# 4port.net
KiCad netlist of a schematic drawn in EAGLE
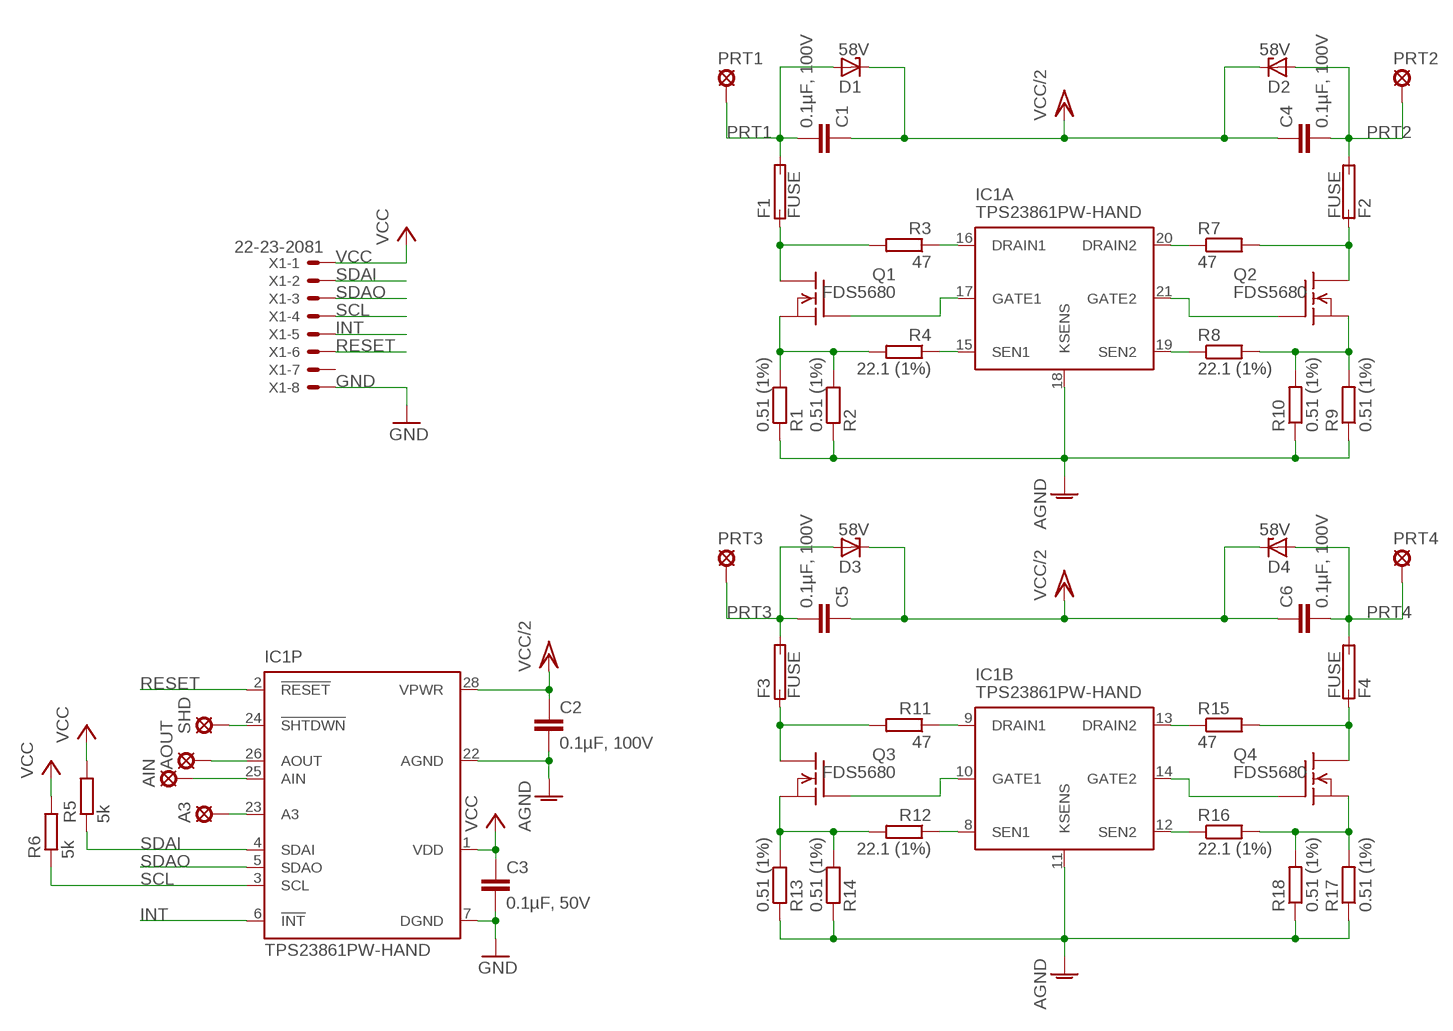
[diagram p0: schematic, sheet 1]
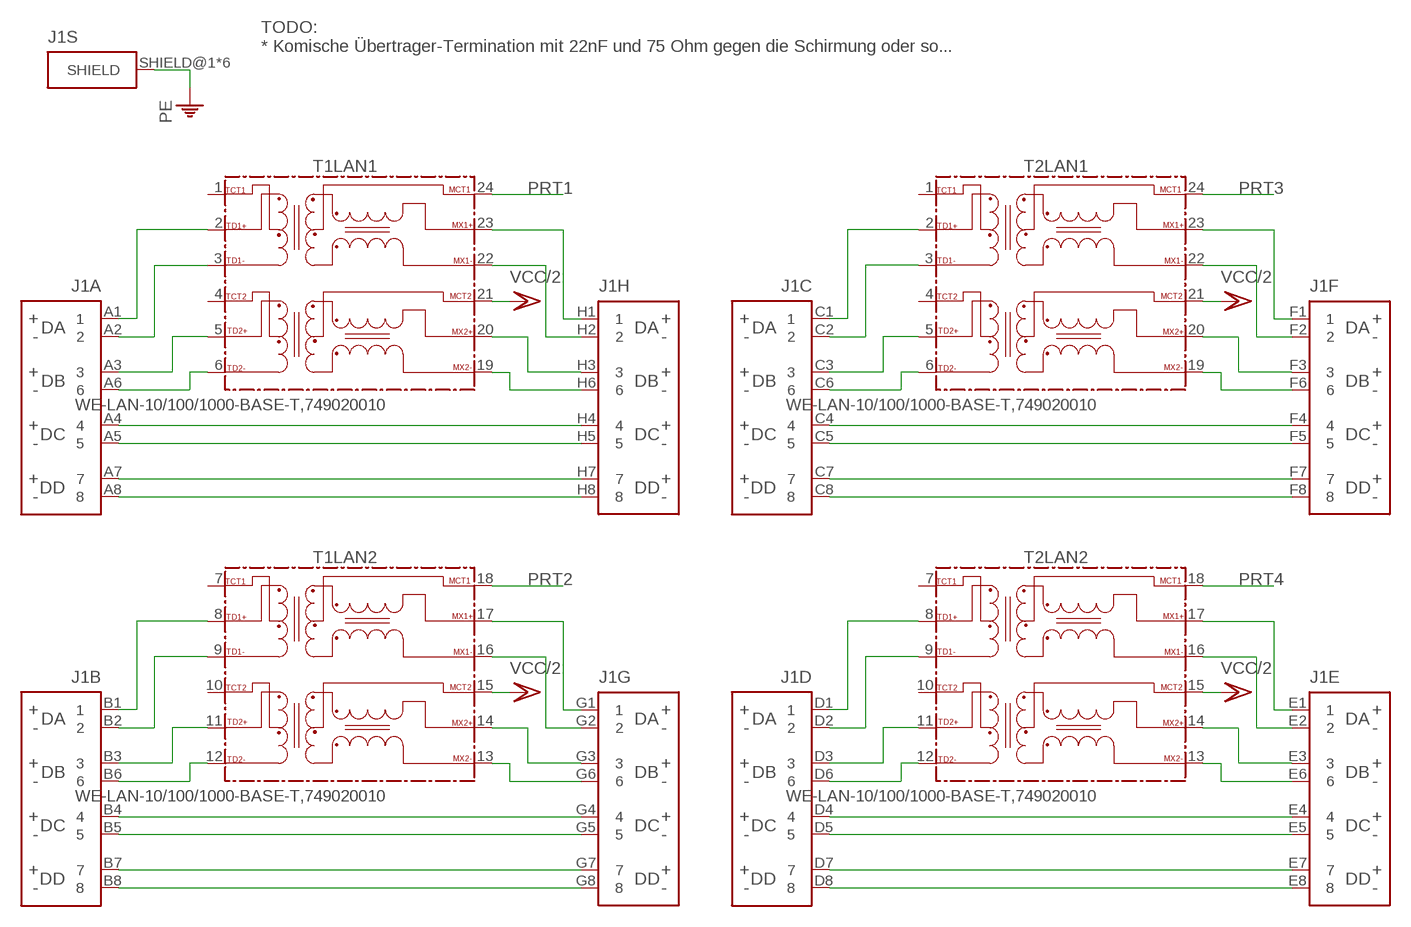
[diagram p1: schematic, sheet 2]
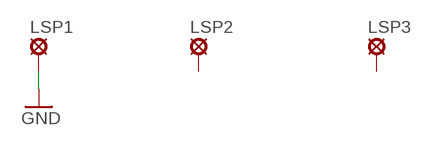
[diagram p2: schematic, sheet 3]

(export (version "E")
  (design (tool "Eeschema 10.0.6"))
  (components
    (comp (ref "J1")
      (value "615064243321")
      (footprint "eagle-import:615064243321")
      (libsource (lib "eagle-import") (part "615064243321"))
    )
    (comp (ref "T1")
      (value "WE-LAN-10/100/1000-BASE-T,749020010")
      (footprint "eagle-import:749020010")
      (fields
        (field (name "MANUFACTURER") "Würth Elektronik eiSos GmbH")
        (field (name "CREATED-BY") "Christin Zierenner")
      )
      (libsource (lib "eagle-import") (part "WE-LAN-10/100/1000-BASE-T,749020010"))
    )
    (comp (ref "T2")
      (value "WE-LAN-10/100/1000-BASE-T,749020010")
      (footprint "eagle-import:749020010")
      (fields
        (field (name "MANUFACTURER") "Würth Elektronik eiSos GmbH")
        (field (name "CREATED-BY") "Christin Zierenner")
      )
      (libsource (lib "eagle-import") (part "WE-LAN-10/100/1000-BASE-T,749020010"))
    )
    (comp (ref "A3")
      (value "SE14")
      (footprint "eagle-import:SE14")
      (libsource (lib "eagle-import") (part "SE14"))
    )
    (comp (ref "AIN")
      (value "SE14")
      (footprint "eagle-import:SE14")
      (libsource (lib "eagle-import") (part "SE14"))
    )
    (comp (ref "AOUT")
      (value "SE14")
      (footprint "eagle-import:SE14")
      (libsource (lib "eagle-import") (part "SE14"))
    )
    (comp (ref "C1")
      (value "0.1µF, 100V")
      (footprint "eagle-import:C0805K")
      (libsource (lib "eagle-import") (part "C-EUC0805K"))
    )
    (comp (ref "C2")
      (value "0.1µF, 100V")
      (footprint "eagle-import:C0805K")
      (libsource (lib "eagle-import") (part "C-EUC0805K"))
    )
    (comp (ref "C3")
      (value "0.1µF, 50V")
      (footprint "eagle-import:C0805K")
      (libsource (lib "eagle-import") (part "C-EUC0805K"))
    )
    (comp (ref "C4")
      (value "0.1µF, 100V")
      (footprint "eagle-import:C0805K")
      (libsource (lib "eagle-import") (part "C-EUC0805K"))
    )
    (comp (ref "C5")
      (value "0.1µF, 100V")
      (footprint "eagle-import:C0805K")
      (libsource (lib "eagle-import") (part "C-EUC0805K"))
    )
    (comp (ref "C6")
      (value "0.1µF, 100V")
      (footprint "eagle-import:C0805K")
      (libsource (lib "eagle-import") (part "C-EUC0805K"))
    )
    (comp (ref "D1")
      (value "58V")
      (footprint "eagle-import:SMB")
      (libsource (lib "eagle-import") (part "ZENER-DIODESMB"))
    )
    (comp (ref "D2")
      (value "58V")
      (footprint "eagle-import:SMB")
      (libsource (lib "eagle-import") (part "ZENER-DIODESMB"))
    )
    (comp (ref "D3")
      (value "58V")
      (footprint "eagle-import:SMB")
      (libsource (lib "eagle-import") (part "ZENER-DIODESMB"))
    )
    (comp (ref "D4")
      (value "58V")
      (footprint "eagle-import:SMB")
      (libsource (lib "eagle-import") (part "ZENER-DIODESMB"))
    )
    (comp (ref "F1")
      (value "FUSE")
      (footprint "eagle-import:R1206W")
      (libsource (lib "eagle-import") (part "FUSE"))
    )
    (comp (ref "F2")
      (value "FUSE")
      (footprint "eagle-import:R1206W")
      (libsource (lib "eagle-import") (part "FUSE"))
    )
    (comp (ref "F3")
      (value "FUSE")
      (footprint "eagle-import:R1206W")
      (libsource (lib "eagle-import") (part "FUSE"))
    )
    (comp (ref "F4")
      (value "FUSE")
      (footprint "eagle-import:R1206W")
      (libsource (lib "eagle-import") (part "FUSE"))
    )
    (comp (ref "IC1")
      (value "TPS23861PW-HAND")
      (footprint "eagle-import:PW_R-PDSO-G28_HAND")
      (libsource (lib "eagle-import") (part "TPS23861PW-HAND"))
    )
    (comp (ref "PRT1")
      (value "SE14")
      (footprint "eagle-import:SE14")
      (libsource (lib "eagle-import") (part "SE14"))
    )
    (comp (ref "PRT2")
      (value "SE14")
      (footprint "eagle-import:SE14")
      (libsource (lib "eagle-import") (part "SE14"))
    )
    (comp (ref "PRT3")
      (value "SE14")
      (footprint "eagle-import:SE14")
      (libsource (lib "eagle-import") (part "SE14"))
    )
    (comp (ref "PRT4")
      (value "SE14")
      (footprint "eagle-import:SE14")
      (libsource (lib "eagle-import") (part "SE14"))
    )
    (comp (ref "Q1")
      (value "FDS5680")
      (footprint "eagle-import:SO-8")
      (libsource (lib "eagle-import") (part "FDS5680"))
    )
    (comp (ref "Q2")
      (value "FDS5680")
      (footprint "eagle-import:SO-8")
      (libsource (lib "eagle-import") (part "FDS5680"))
    )
    (comp (ref "Q3")
      (value "FDS5680")
      (footprint "eagle-import:SO-8")
      (libsource (lib "eagle-import") (part "FDS5680"))
    )
    (comp (ref "Q4")
      (value "FDS5680")
      (footprint "eagle-import:SO-8")
      (libsource (lib "eagle-import") (part "FDS5680"))
    )
    (comp (ref "R1")
      (value "0.51 (1%)")
      (footprint "eagle-import:R0603")
      (libsource (lib "eagle-import") (part "R-EU_R0603"))
    )
    (comp (ref "R2")
      (value "0.51 (1%)")
      (footprint "eagle-import:R0603")
      (libsource (lib "eagle-import") (part "R-EU_R0603"))
    )
    (comp (ref "R3")
      (value "47")
      (footprint "eagle-import:R0603")
      (libsource (lib "eagle-import") (part "R-EU_R0603"))
    )
    (comp (ref "R4")
      (value "22.1 (1%)")
      (footprint "eagle-import:R0603")
      (libsource (lib "eagle-import") (part "R-EU_R0603"))
    )
    (comp (ref "R5")
      (value "5k")
      (footprint "eagle-import:R0805W")
      (libsource (lib "eagle-import") (part "R-EU_R0805W"))
    )
    (comp (ref "R6")
      (value "5k")
      (footprint "eagle-import:R0805W")
      (libsource (lib "eagle-import") (part "R-EU_R0805W"))
    )
    (comp (ref "R7")
      (value "47")
      (footprint "eagle-import:R0603")
      (libsource (lib "eagle-import") (part "R-EU_R0603"))
    )
    (comp (ref "R8")
      (value "22.1 (1%)")
      (footprint "eagle-import:R0603")
      (libsource (lib "eagle-import") (part "R-EU_R0603"))
    )
    (comp (ref "R9")
      (value "0.51 (1%)")
      (footprint "eagle-import:R0603")
      (libsource (lib "eagle-import") (part "R-EU_R0603"))
    )
    (comp (ref "R10")
      (value "0.51 (1%)")
      (footprint "eagle-import:R0603")
      (libsource (lib "eagle-import") (part "R-EU_R0603"))
    )
    (comp (ref "R11")
      (value "47")
      (footprint "eagle-import:R0603")
      (libsource (lib "eagle-import") (part "R-EU_R0603"))
    )
    (comp (ref "R12")
      (value "22.1 (1%)")
      (footprint "eagle-import:R0603")
      (libsource (lib "eagle-import") (part "R-EU_R0603"))
    )
    (comp (ref "R13")
      (value "0.51 (1%)")
      (footprint "eagle-import:R0603")
      (libsource (lib "eagle-import") (part "R-EU_R0603"))
    )
    (comp (ref "R14")
      (value "0.51 (1%)")
      (footprint "eagle-import:R0603")
      (libsource (lib "eagle-import") (part "R-EU_R0603"))
    )
    (comp (ref "R15")
      (value "47")
      (footprint "eagle-import:R0603")
      (libsource (lib "eagle-import") (part "R-EU_R0603"))
    )
    (comp (ref "R16")
      (value "22.1 (1%)")
      (footprint "eagle-import:R0603")
      (libsource (lib "eagle-import") (part "R-EU_R0603"))
    )
    (comp (ref "R17")
      (value "0.51 (1%)")
      (footprint "eagle-import:R0603")
      (libsource (lib "eagle-import") (part "R-EU_R0603"))
    )
    (comp (ref "R18")
      (value "0.51 (1%)")
      (footprint "eagle-import:R0603")
      (libsource (lib "eagle-import") (part "R-EU_R0603"))
    )
    (comp (ref "SHD")
      (value "SE14")
      (footprint "eagle-import:SE14")
      (libsource (lib "eagle-import") (part "SE14"))
    )
    (comp (ref "X1")
      (value "22-23-2081")
      (footprint "eagle-import:22-23-2081")
      (fields (field (name "MF") "MOLEX"))
      (libsource (lib "eagle-import") (part "22-23-2081"))
    )
    (comp (ref "LSP1")
      (value "SE14")
      (footprint "eagle-import:SE14")
      (libsource (lib "eagle-import") (part "SE14"))
    )
    (comp (ref "LSP2")
      (value "SE14")
      (footprint "eagle-import:SE14")
      (libsource (lib "eagle-import") (part "SE14"))
    )
    (comp (ref "LSP3")
      (value "SE14")
      (footprint "eagle-import:SE14")
      (libsource (lib "eagle-import") (part "SE14"))
    )
  )
  (nets
    (net (code "1") (name "AGND") (class "Default")
      (node (ref "C2") (pin "2") (pinfunction "2_2") (pintype "passive"))
      (node (ref "IC1") (pin "11") (pinfunction "KSENS_11") (pintype "input"))
      (node (ref "IC1") (pin "18") (pinfunction "KSENS_18") (pintype "input"))
      (node (ref "IC1") (pin "22") (pinfunction "AGND_22") (pintype "power_in"))
      (node (ref "R1") (pin "1") (pinfunction "1_1") (pintype "passive"))
      (node (ref "R10") (pin "1") (pinfunction "1_1") (pintype "passive"))
      (node (ref "R13") (pin "1") (pinfunction "1_1") (pintype "passive"))
      (node (ref "R14") (pin "1") (pinfunction "1_1") (pintype "passive"))
      (node (ref "R17") (pin "1") (pinfunction "1_1") (pintype "passive"))
      (node (ref "R18") (pin "1") (pinfunction "1_1") (pintype "passive"))
      (node (ref "R2") (pin "1") (pinfunction "1_1") (pintype "passive"))
      (node (ref "R9") (pin "1") (pinfunction "1_1") (pintype "passive"))
    )
    (net (code "2") (name "GND") (class "Default")
      (node (ref "C3") (pin "2") (pinfunction "2_2") (pintype "passive"))
      (node (ref "IC1") (pin "7") (pinfunction "DGND_7") (pintype "power_in"))
      (node (ref "LSP1") (pin "MP") (pinfunction "MP_MP") (pintype "passive"))
      (node (ref "X1") (pin "8") (pinfunction "S_8") (pintype "passive"))
    )
    (net (code "3") (name "INT") (class "Default")
      (node (ref "IC1") (pin "6") (pinfunction "~{INT}_6") (pintype "output"))
      (node (ref "X1") (pin "5") (pinfunction "S_5") (pintype "passive"))
    )
    (net (code "4") (name "Net-(F1-1A)") (class "Default")
      (node (ref "F1") (pin "1") (pinfunction "1A_1") (pintype "passive"))
      (node (ref "Q1") (pin "5") (pinfunction "D_5") (pintype "passive"))
      (node (ref "Q1") (pin "6") (pinfunction "D_6") (pintype "passive"))
      (node (ref "Q1") (pin "7") (pinfunction "D_7") (pintype "passive"))
      (node (ref "Q1") (pin "8") (pinfunction "D_8") (pintype "passive"))
      (node (ref "R3") (pin "2") (pinfunction "2_2") (pintype "passive"))
    )
    (net (code "5") (name "Net-(F2-1A)") (class "Default")
      (node (ref "F2") (pin "1") (pinfunction "1A_1") (pintype "passive"))
      (node (ref "Q2") (pin "5") (pinfunction "D_5") (pintype "passive"))
      (node (ref "Q2") (pin "6") (pinfunction "D_6") (pintype "passive"))
      (node (ref "Q2") (pin "7") (pinfunction "D_7") (pintype "passive"))
      (node (ref "Q2") (pin "8") (pinfunction "D_8") (pintype "passive"))
      (node (ref "R7") (pin "2") (pinfunction "2_2") (pintype "passive"))
    )
    (net (code "6") (name "Net-(F3-1A)") (class "Default")
      (node (ref "F3") (pin "1") (pinfunction "1A_1") (pintype "passive"))
      (node (ref "Q3") (pin "5") (pinfunction "D_5") (pintype "passive"))
      (node (ref "Q3") (pin "6") (pinfunction "D_6") (pintype "passive"))
      (node (ref "Q3") (pin "7") (pinfunction "D_7") (pintype "passive"))
      (node (ref "Q3") (pin "8") (pinfunction "D_8") (pintype "passive"))
      (node (ref "R11") (pin "2") (pinfunction "2_2") (pintype "passive"))
    )
    (net (code "7") (name "Net-(F4-1A)") (class "Default")
      (node (ref "F4") (pin "1") (pinfunction "1A_1") (pintype "passive"))
      (node (ref "Q4") (pin "5") (pinfunction "D_5") (pintype "passive"))
      (node (ref "Q4") (pin "6") (pinfunction "D_6") (pintype "passive"))
      (node (ref "Q4") (pin "7") (pinfunction "D_7") (pintype "passive"))
      (node (ref "Q4") (pin "8") (pinfunction "D_8") (pintype "passive"))
      (node (ref "R15") (pin "2") (pinfunction "2_2") (pintype "passive"))
    )
    (net (code "8") (name "Net-(IC1A-DRAIN1)") (class "Default")
      (node (ref "IC1") (pin "16") (pinfunction "DRAIN1_16") (pintype "input"))
      (node (ref "R3") (pin "1") (pinfunction "1_1") (pintype "passive"))
    )
    (net (code "9") (name "Net-(IC1A-DRAIN2)") (class "Default")
      (node (ref "IC1") (pin "20") (pinfunction "DRAIN2_20") (pintype "input"))
      (node (ref "R7") (pin "1") (pinfunction "1_1") (pintype "passive"))
    )
    (net (code "10") (name "Net-(IC1A-GATE1)") (class "Default")
      (node (ref "IC1") (pin "17") (pinfunction "GATE1_17") (pintype "output"))
      (node (ref "Q1") (pin "4") (pinfunction "G_4") (pintype "passive"))
    )
    (net (code "11") (name "Net-(IC1A-GATE2)") (class "Default")
      (node (ref "IC1") (pin "21") (pinfunction "GATE2_21") (pintype "output"))
      (node (ref "Q2") (pin "4") (pinfunction "G_4") (pintype "passive"))
    )
    (net (code "12") (name "Net-(IC1A-SEN1)") (class "Default")
      (node (ref "IC1") (pin "15") (pinfunction "SEN1_15") (pintype "input"))
      (node (ref "R4") (pin "1") (pinfunction "1_1") (pintype "passive"))
    )
    (net (code "13") (name "Net-(IC1A-SEN2)") (class "Default")
      (node (ref "IC1") (pin "19") (pinfunction "SEN2_19") (pintype "input"))
      (node (ref "R8") (pin "1") (pinfunction "1_1") (pintype "passive"))
    )
    (net (code "14") (name "Net-(IC1B-DRAIN1)") (class "Default")
      (node (ref "IC1") (pin "9") (pinfunction "DRAIN1_9") (pintype "input"))
      (node (ref "R11") (pin "1") (pinfunction "1_1") (pintype "passive"))
    )
    (net (code "15") (name "Net-(IC1B-DRAIN2)") (class "Default")
      (node (ref "IC1") (pin "13") (pinfunction "DRAIN2_13") (pintype "input"))
      (node (ref "R15") (pin "1") (pinfunction "1_1") (pintype "passive"))
    )
    (net (code "16") (name "Net-(IC1B-GATE1)") (class "Default")
      (node (ref "IC1") (pin "10") (pinfunction "GATE1_10") (pintype "output"))
      (node (ref "Q3") (pin "4") (pinfunction "G_4") (pintype "passive"))
    )
    (net (code "17") (name "Net-(IC1B-GATE2)") (class "Default")
      (node (ref "IC1") (pin "14") (pinfunction "GATE2_14") (pintype "output"))
      (node (ref "Q4") (pin "4") (pinfunction "G_4") (pintype "passive"))
    )
    (net (code "18") (name "Net-(IC1B-SEN1)") (class "Default")
      (node (ref "IC1") (pin "8") (pinfunction "SEN1_8") (pintype "input"))
      (node (ref "R12") (pin "1") (pinfunction "1_1") (pintype "passive"))
    )
    (net (code "19") (name "Net-(IC1B-SEN2)") (class "Default")
      (node (ref "IC1") (pin "12") (pinfunction "SEN2_12") (pintype "input"))
      (node (ref "R16") (pin "1") (pinfunction "1_1") (pintype "passive"))
    )
    (net (code "20") (name "Net-(IC1C-A3)") (class "Default")
      (node (ref "A3") (pin "MP") (pinfunction "MP_MP") (pintype "passive"))
      (node (ref "IC1") (pin "23") (pinfunction "A3_23") (pintype "input"))
    )
    (net (code "21") (name "Net-(IC1C-AIN)") (class "Default")
      (node (ref "AIN") (pin "MP") (pinfunction "MP_MP") (pintype "passive"))
      (node (ref "IC1") (pin "25") (pinfunction "AIN_25") (pintype "input"))
    )
    (net (code "22") (name "Net-(IC1C-AOUT)") (class "Default")
      (node (ref "AOUT") (pin "MP") (pinfunction "MP_MP") (pintype "passive"))
      (node (ref "IC1") (pin "26") (pinfunction "AOUT_26") (pintype "output"))
    )
    (net (code "23") (name "Net-(IC1C-~{SHTDWN})") (class "Default")
      (node (ref "IC1") (pin "24") (pinfunction "~{SHTDWN}_24") (pintype "input"))
      (node (ref "SHD") (pin "MP") (pinfunction "MP_MP") (pintype "passive"))
    )
    (net (code "24") (name "Net-(J1A-1)") (class "Default")
      (node (ref "J1") (pin "A1") (pinfunction "1_A1") (pintype "passive"))
      (node (ref "T1") (pin "2") (pinfunction "TD1+_2") (pintype "bidirectional"))
    )
    (net (code "25") (name "Net-(J1A-2)") (class "Default")
      (node (ref "J1") (pin "A2") (pinfunction "2_A2") (pintype "passive"))
      (node (ref "T1") (pin "3") (pinfunction "TD1-_3") (pintype "bidirectional"))
    )
    (net (code "26") (name "Net-(J1A-3)") (class "Default")
      (node (ref "J1") (pin "A3") (pinfunction "3_A3") (pintype "passive"))
      (node (ref "T1") (pin "5") (pinfunction "TD2+_5") (pintype "bidirectional"))
    )
    (net (code "27") (name "Net-(J1A-4)") (class "Default")
      (node (ref "J1") (pin "A4") (pinfunction "4_A4") (pintype "passive"))
      (node (ref "J1") (pin "H4") (pinfunction "4_H4") (pintype "passive"))
    )
    (net (code "28") (name "Net-(J1A-5)") (class "Default")
      (node (ref "J1") (pin "A5") (pinfunction "5_A5") (pintype "passive"))
      (node (ref "J1") (pin "H5") (pinfunction "5_H5") (pintype "passive"))
    )
    (net (code "29") (name "Net-(J1A-6)") (class "Default")
      (node (ref "J1") (pin "A6") (pinfunction "6_A6") (pintype "passive"))
      (node (ref "T1") (pin "6") (pinfunction "TD2-_6") (pintype "bidirectional"))
    )
    (net (code "30") (name "Net-(J1A-7)") (class "Default")
      (node (ref "J1") (pin "A7") (pinfunction "7_A7") (pintype "passive"))
      (node (ref "J1") (pin "H7") (pinfunction "7_H7") (pintype "passive"))
    )
    (net (code "31") (name "Net-(J1A-8)") (class "Default")
      (node (ref "J1") (pin "A8") (pinfunction "8_A8") (pintype "passive"))
      (node (ref "J1") (pin "H8") (pinfunction "8_H8") (pintype "passive"))
    )
    (net (code "32") (name "Net-(J1B-1)") (class "Default")
      (node (ref "J1") (pin "B1") (pinfunction "1_B1") (pintype "passive"))
      (node (ref "T1") (pin "8") (pinfunction "TD1+_8") (pintype "bidirectional"))
    )
    (net (code "33") (name "Net-(J1B-2)") (class "Default")
      (node (ref "J1") (pin "B2") (pinfunction "2_B2") (pintype "passive"))
      (node (ref "T1") (pin "9") (pinfunction "TD1-_9") (pintype "bidirectional"))
    )
    (net (code "34") (name "Net-(J1B-3)") (class "Default")
      (node (ref "J1") (pin "B3") (pinfunction "3_B3") (pintype "passive"))
      (node (ref "T1") (pin "11") (pinfunction "TD2+_11") (pintype "bidirectional"))
    )
    (net (code "35") (name "Net-(J1B-4)") (class "Default")
      (node (ref "J1") (pin "B4") (pinfunction "4_B4") (pintype "passive"))
      (node (ref "J1") (pin "G4") (pinfunction "4_G4") (pintype "passive"))
    )
    (net (code "36") (name "Net-(J1B-5)") (class "Default")
      (node (ref "J1") (pin "B5") (pinfunction "5_B5") (pintype "passive"))
      (node (ref "J1") (pin "G5") (pinfunction "5_G5") (pintype "passive"))
    )
    (net (code "37") (name "Net-(J1B-6)") (class "Default")
      (node (ref "J1") (pin "B6") (pinfunction "6_B6") (pintype "passive"))
      (node (ref "T1") (pin "12") (pinfunction "TD2-_12") (pintype "bidirectional"))
    )
    (net (code "38") (name "Net-(J1B-7)") (class "Default")
      (node (ref "J1") (pin "B7") (pinfunction "7_B7") (pintype "passive"))
      (node (ref "J1") (pin "G7") (pinfunction "7_G7") (pintype "passive"))
    )
    (net (code "39") (name "Net-(J1B-8)") (class "Default")
      (node (ref "J1") (pin "B8") (pinfunction "8_B8") (pintype "passive"))
      (node (ref "J1") (pin "G8") (pinfunction "8_G8") (pintype "passive"))
    )
    (net (code "40") (name "Net-(J1C-1)") (class "Default")
      (node (ref "J1") (pin "C1") (pinfunction "1_C1") (pintype "passive"))
      (node (ref "T2") (pin "2") (pinfunction "TD1+_2") (pintype "bidirectional"))
    )
    (net (code "41") (name "Net-(J1C-2)") (class "Default")
      (node (ref "J1") (pin "C2") (pinfunction "2_C2") (pintype "passive"))
      (node (ref "T2") (pin "3") (pinfunction "TD1-_3") (pintype "bidirectional"))
    )
    (net (code "42") (name "Net-(J1C-3)") (class "Default")
      (node (ref "J1") (pin "C3") (pinfunction "3_C3") (pintype "passive"))
      (node (ref "T2") (pin "5") (pinfunction "TD2+_5") (pintype "bidirectional"))
    )
    (net (code "43") (name "Net-(J1C-4)") (class "Default")
      (node (ref "J1") (pin "C4") (pinfunction "4_C4") (pintype "passive"))
      (node (ref "J1") (pin "F4") (pinfunction "4_F4") (pintype "passive"))
    )
    (net (code "44") (name "Net-(J1C-5)") (class "Default")
      (node (ref "J1") (pin "C5") (pinfunction "5_C5") (pintype "passive"))
      (node (ref "J1") (pin "F5") (pinfunction "5_F5") (pintype "passive"))
    )
    (net (code "45") (name "Net-(J1C-6)") (class "Default")
      (node (ref "J1") (pin "C6") (pinfunction "6_C6") (pintype "passive"))
      (node (ref "T2") (pin "6") (pinfunction "TD2-_6") (pintype "bidirectional"))
    )
    (net (code "46") (name "Net-(J1C-7)") (class "Default")
      (node (ref "J1") (pin "C7") (pinfunction "7_C7") (pintype "passive"))
      (node (ref "J1") (pin "F7") (pinfunction "7_F7") (pintype "passive"))
    )
    (net (code "47") (name "Net-(J1C-8)") (class "Default")
      (node (ref "J1") (pin "C8") (pinfunction "8_C8") (pintype "passive"))
      (node (ref "J1") (pin "F8") (pinfunction "8_F8") (pintype "passive"))
    )
    (net (code "48") (name "Net-(J1D-1)") (class "Default")
      (node (ref "J1") (pin "D1") (pinfunction "1_D1") (pintype "passive"))
      (node (ref "T2") (pin "8") (pinfunction "TD1+_8") (pintype "bidirectional"))
    )
    (net (code "49") (name "Net-(J1D-2)") (class "Default")
      (node (ref "J1") (pin "D2") (pinfunction "2_D2") (pintype "passive"))
      (node (ref "T2") (pin "9") (pinfunction "TD1-_9") (pintype "bidirectional"))
    )
    (net (code "50") (name "Net-(J1D-3)") (class "Default")
      (node (ref "J1") (pin "D3") (pinfunction "3_D3") (pintype "passive"))
      (node (ref "T2") (pin "11") (pinfunction "TD2+_11") (pintype "bidirectional"))
    )
    (net (code "51") (name "Net-(J1D-4)") (class "Default")
      (node (ref "J1") (pin "D4") (pinfunction "4_D4") (pintype "passive"))
      (node (ref "J1") (pin "E4") (pinfunction "4_E4") (pintype "passive"))
    )
    (net (code "52") (name "Net-(J1D-5)") (class "Default")
      (node (ref "J1") (pin "D5") (pinfunction "5_D5") (pintype "passive"))
      (node (ref "J1") (pin "E5") (pinfunction "5_E5") (pintype "passive"))
    )
    (net (code "53") (name "Net-(J1D-6)") (class "Default")
      (node (ref "J1") (pin "D6") (pinfunction "6_D6") (pintype "passive"))
      (node (ref "T2") (pin "12") (pinfunction "TD2-_12") (pintype "bidirectional"))
    )
    (net (code "54") (name "Net-(J1D-7)") (class "Default")
      (node (ref "J1") (pin "D7") (pinfunction "7_D7") (pintype "passive"))
      (node (ref "J1") (pin "E7") (pinfunction "7_E7") (pintype "passive"))
    )
    (net (code "55") (name "Net-(J1D-8)") (class "Default")
      (node (ref "J1") (pin "D8") (pinfunction "8_D8") (pintype "passive"))
      (node (ref "J1") (pin "E8") (pinfunction "8_E8") (pintype "passive"))
    )
    (net (code "56") (name "Net-(J1E-1)") (class "Default")
      (node (ref "J1") (pin "E1") (pinfunction "1_E1") (pintype "passive"))
      (node (ref "T2") (pin "17") (pinfunction "MX1+_17") (pintype "bidirectional"))
    )
    (net (code "57") (name "Net-(J1E-2)") (class "Default")
      (node (ref "J1") (pin "E2") (pinfunction "2_E2") (pintype "passive"))
      (node (ref "T2") (pin "16") (pinfunction "MX1-_16") (pintype "bidirectional"))
    )
    (net (code "58") (name "Net-(J1E-3)") (class "Default")
      (node (ref "J1") (pin "E3") (pinfunction "3_E3") (pintype "passive"))
      (node (ref "T2") (pin "14") (pinfunction "MX2+_14") (pintype "bidirectional"))
    )
    (net (code "59") (name "Net-(J1E-6)") (class "Default")
      (node (ref "J1") (pin "E6") (pinfunction "6_E6") (pintype "passive"))
      (node (ref "T2") (pin "13") (pinfunction "MX2-_13") (pintype "bidirectional"))
    )
    (net (code "60") (name "Net-(J1F-1)") (class "Default")
      (node (ref "J1") (pin "F1") (pinfunction "1_F1") (pintype "passive"))
      (node (ref "T2") (pin "23") (pinfunction "MX1+_23") (pintype "bidirectional"))
    )
    (net (code "61") (name "Net-(J1F-2)") (class "Default")
      (node (ref "J1") (pin "F2") (pinfunction "2_F2") (pintype "passive"))
      (node (ref "T2") (pin "22") (pinfunction "MX1-_22") (pintype "bidirectional"))
    )
    (net (code "62") (name "Net-(J1F-3)") (class "Default")
      (node (ref "J1") (pin "F3") (pinfunction "3_F3") (pintype "passive"))
      (node (ref "T2") (pin "20") (pinfunction "MX2+_20") (pintype "bidirectional"))
    )
    (net (code "63") (name "Net-(J1F-6)") (class "Default")
      (node (ref "J1") (pin "F6") (pinfunction "6_F6") (pintype "passive"))
      (node (ref "T2") (pin "19") (pinfunction "MX2-_19") (pintype "bidirectional"))
    )
    (net (code "64") (name "Net-(J1G-1)") (class "Default")
      (node (ref "J1") (pin "G1") (pinfunction "1_G1") (pintype "passive"))
      (node (ref "T1") (pin "17") (pinfunction "MX1+_17") (pintype "bidirectional"))
    )
    (net (code "65") (name "Net-(J1G-2)") (class "Default")
      (node (ref "J1") (pin "G2") (pinfunction "2_G2") (pintype "passive"))
      (node (ref "T1") (pin "16") (pinfunction "MX1-_16") (pintype "bidirectional"))
    )
    (net (code "66") (name "Net-(J1G-3)") (class "Default")
      (node (ref "J1") (pin "G3") (pinfunction "3_G3") (pintype "passive"))
      (node (ref "T1") (pin "14") (pinfunction "MX2+_14") (pintype "bidirectional"))
    )
    (net (code "67") (name "Net-(J1G-6)") (class "Default")
      (node (ref "J1") (pin "G6") (pinfunction "6_G6") (pintype "passive"))
      (node (ref "T1") (pin "13") (pinfunction "MX2-_13") (pintype "bidirectional"))
    )
    (net (code "68") (name "Net-(J1H-1)") (class "Default")
      (node (ref "J1") (pin "H1") (pinfunction "1_H1") (pintype "passive"))
      (node (ref "T1") (pin "23") (pinfunction "MX1+_23") (pintype "bidirectional"))
    )
    (net (code "69") (name "Net-(J1H-2)") (class "Default")
      (node (ref "J1") (pin "H2") (pinfunction "2_H2") (pintype "passive"))
      (node (ref "T1") (pin "22") (pinfunction "MX1-_22") (pintype "bidirectional"))
    )
    (net (code "70") (name "Net-(J1H-3)") (class "Default")
      (node (ref "J1") (pin "H3") (pinfunction "3_H3") (pintype "passive"))
      (node (ref "T1") (pin "20") (pinfunction "MX2+_20") (pintype "bidirectional"))
    )
    (net (code "71") (name "Net-(J1H-6)") (class "Default")
      (node (ref "J1") (pin "H6") (pinfunction "6_H6") (pintype "passive"))
      (node (ref "T1") (pin "19") (pinfunction "MX2-_19") (pintype "bidirectional"))
    )
    (net (code "72") (name "Net-(Q1-S-Pad1)") (class "Default")
      (node (ref "Q1") (pin "1") (pinfunction "S_1") (pintype "passive"))
      (node (ref "Q1") (pin "2") (pinfunction "S_2") (pintype "passive"))
      (node (ref "Q1") (pin "3") (pinfunction "S_3") (pintype "passive"))
      (node (ref "R1") (pin "2") (pinfunction "2_2") (pintype "passive"))
      (node (ref "R2") (pin "2") (pinfunction "2_2") (pintype "passive"))
      (node (ref "R4") (pin "2") (pinfunction "2_2") (pintype "passive"))
    )
    (net (code "73") (name "Net-(Q2-S-Pad1)") (class "Default")
      (node (ref "Q2") (pin "1") (pinfunction "S_1") (pintype "passive"))
      (node (ref "Q2") (pin "2") (pinfunction "S_2") (pintype "passive"))
      (node (ref "Q2") (pin "3") (pinfunction "S_3") (pintype "passive"))
      (node (ref "R10") (pin "2") (pinfunction "2_2") (pintype "passive"))
      (node (ref "R8") (pin "2") (pinfunction "2_2") (pintype "passive"))
      (node (ref "R9") (pin "2") (pinfunction "2_2") (pintype "passive"))
    )
    (net (code "74") (name "Net-(Q3-S-Pad1)") (class "Default")
      (node (ref "Q3") (pin "1") (pinfunction "S_1") (pintype "passive"))
      (node (ref "Q3") (pin "2") (pinfunction "S_2") (pintype "passive"))
      (node (ref "Q3") (pin "3") (pinfunction "S_3") (pintype "passive"))
      (node (ref "R12") (pin "2") (pinfunction "2_2") (pintype "passive"))
      (node (ref "R13") (pin "2") (pinfunction "2_2") (pintype "passive"))
      (node (ref "R14") (pin "2") (pinfunction "2_2") (pintype "passive"))
    )
    (net (code "75") (name "Net-(Q4-S-Pad1)") (class "Default")
      (node (ref "Q4") (pin "1") (pinfunction "S_1") (pintype "passive"))
      (node (ref "Q4") (pin "2") (pinfunction "S_2") (pintype "passive"))
      (node (ref "Q4") (pin "3") (pinfunction "S_3") (pintype "passive"))
      (node (ref "R16") (pin "2") (pinfunction "2_2") (pintype "passive"))
      (node (ref "R17") (pin "2") (pinfunction "2_2") (pintype "passive"))
      (node (ref "R18") (pin "2") (pinfunction "2_2") (pintype "passive"))
    )
    (net (code "76") (name "PE") (class "Default")
      (node (ref "J1") (pin "SHIELD@1") (pinfunction "SHIELD_SHIELD@1") (pintype "passive"))
      (node (ref "J1") (pin "SHIELD@2") (pinfunction "SHIELD_SHIELD@2") (pintype "passive"))
      (node (ref "J1") (pin "SHIELD@3") (pinfunction "SHIELD_SHIELD@3") (pintype "passive"))
      (node (ref "J1") (pin "SHIELD@4") (pinfunction "SHIELD_SHIELD@4") (pintype "passive"))
      (node (ref "J1") (pin "SHIELD@5") (pinfunction "SHIELD_SHIELD@5") (pintype "passive"))
      (node (ref "J1") (pin "SHIELD@6") (pinfunction "SHIELD_SHIELD@6") (pintype "passive"))
    )
    (net (code "77") (name "PRT1") (class "Default")
      (node (ref "C1") (pin "2") (pinfunction "2_2") (pintype "passive"))
      (node (ref "D1") (pin "A") (pinfunction "A_A") (pintype "passive"))
      (node (ref "F1") (pin "2") (pinfunction "2A_2") (pintype "passive"))
      (node (ref "PRT1") (pin "MP") (pinfunction "MP_MP") (pintype "passive"))
      (node (ref "T1") (pin "24") (pinfunction "MCT1_24") (pintype "bidirectional"))
    )
    (net (code "78") (name "PRT2") (class "Default")
      (node (ref "C4") (pin "2") (pinfunction "2_2") (pintype "passive"))
      (node (ref "D2") (pin "A") (pinfunction "A_A") (pintype "passive"))
      (node (ref "F2") (pin "2") (pinfunction "2A_2") (pintype "passive"))
      (node (ref "PRT2") (pin "MP") (pinfunction "MP_MP") (pintype "passive"))
      (node (ref "T1") (pin "18") (pinfunction "MCT1_18") (pintype "bidirectional"))
    )
    (net (code "79") (name "PRT3") (class "Default")
      (node (ref "C5") (pin "2") (pinfunction "2_2") (pintype "passive"))
      (node (ref "D3") (pin "A") (pinfunction "A_A") (pintype "passive"))
      (node (ref "F3") (pin "2") (pinfunction "2A_2") (pintype "passive"))
      (node (ref "PRT3") (pin "MP") (pinfunction "MP_MP") (pintype "passive"))
      (node (ref "T2") (pin "24") (pinfunction "MCT1_24") (pintype "bidirectional"))
    )
    (net (code "80") (name "PRT4") (class "Default")
      (node (ref "C6") (pin "2") (pinfunction "2_2") (pintype "passive"))
      (node (ref "D4") (pin "A") (pinfunction "A_A") (pintype "passive"))
      (node (ref "F4") (pin "2") (pinfunction "2A_2") (pintype "passive"))
      (node (ref "PRT4") (pin "MP") (pinfunction "MP_MP") (pintype "passive"))
      (node (ref "T2") (pin "18") (pinfunction "MCT1_18") (pintype "bidirectional"))
    )
    (net (code "81") (name "RESET") (class "Default")
      (node (ref "IC1") (pin "2") (pinfunction "~{RESET}_2") (pintype "input"))
      (node (ref "X1") (pin "6") (pinfunction "S_6") (pintype "passive"))
    )
    (net (code "82") (name "SCL") (class "Default")
      (node (ref "IC1") (pin "3") (pinfunction "SCL_3") (pintype "input"))
      (node (ref "R6") (pin "1") (pinfunction "1_1") (pintype "passive"))
      (node (ref "X1") (pin "4") (pinfunction "S_4") (pintype "passive"))
    )
    (net (code "83") (name "SDAI") (class "Default")
      (node (ref "IC1") (pin "4") (pinfunction "SDAI_4") (pintype "input"))
      (node (ref "R5") (pin "1") (pinfunction "1_1") (pintype "passive"))
      (node (ref "X1") (pin "2") (pinfunction "S_2") (pintype "passive"))
    )
    (net (code "84") (name "SDAO") (class "Default")
      (node (ref "IC1") (pin "5") (pinfunction "SDAO_5") (pintype "output"))
      (node (ref "X1") (pin "3") (pinfunction "S_3") (pintype "passive"))
    )
    (net (code "85") (name "VCC") (class "Default")
      (node (ref "C3") (pin "1") (pinfunction "1_1") (pintype "passive"))
      (node (ref "IC1") (pin "1") (pinfunction "VDD_1") (pintype "power_in"))
      (node (ref "R5") (pin "2") (pinfunction "2_2") (pintype "passive"))
      (node (ref "R6") (pin "2") (pinfunction "2_2") (pintype "passive"))
      (node (ref "X1") (pin "1") (pinfunction "S_1") (pintype "passive"))
    )
    (net (code "86") (name "VCC{slash}2") (class "Default")
      (node (ref "C1") (pin "1") (pinfunction "1_1") (pintype "passive"))
      (node (ref "C2") (pin "1") (pinfunction "1_1") (pintype "passive"))
      (node (ref "C4") (pin "1") (pinfunction "1_1") (pintype "passive"))
      (node (ref "C5") (pin "1") (pinfunction "1_1") (pintype "passive"))
      (node (ref "C6") (pin "1") (pinfunction "1_1") (pintype "passive"))
      (node (ref "D1") (pin "C") (pinfunction "C_C") (pintype "passive"))
      (node (ref "D2") (pin "C") (pinfunction "C_C") (pintype "passive"))
      (node (ref "D3") (pin "C") (pinfunction "C_C") (pintype "passive"))
      (node (ref "D4") (pin "C") (pinfunction "C_C") (pintype "passive"))
      (node (ref "IC1") (pin "28") (pinfunction "VPWR_28") (pintype "power_in"))
      (node (ref "T1") (pin "15") (pinfunction "MCT2_15") (pintype "bidirectional"))
      (node (ref "T1") (pin "21") (pinfunction "MCT2_21") (pintype "bidirectional"))
      (node (ref "T2") (pin "15") (pinfunction "MCT2_15") (pintype "bidirectional"))
      (node (ref "T2") (pin "21") (pinfunction "MCT2_21") (pintype "bidirectional"))
    )
    (net (code "87") (name "unconnected-(LSP2-PadMP)") (class "Default")
      (node (ref "LSP2") (pin "MP") (pinfunction "MP_MP") (pintype "passive"))
    )
    (net (code "88") (name "unconnected-(LSP3-PadMP)") (class "Default")
      (node (ref "LSP3") (pin "MP") (pinfunction "MP_MP") (pintype "passive"))
    )
    (net (code "89") (name "unconnected-(T1A-TCT1-Pad1)") (class "Default")
      (node (ref "T1") (pin "1") (pinfunction "TCT1_1") (pintype "bidirectional"))
    )
    (net (code "90") (name "unconnected-(T1A-TCT2-Pad4)") (class "Default")
      (node (ref "T1") (pin "4") (pinfunction "TCT2_4") (pintype "bidirectional"))
    )
    (net (code "91") (name "unconnected-(T1B-TCT1-Pad7)") (class "Default")
      (node (ref "T1") (pin "7") (pinfunction "TCT1_7") (pintype "bidirectional"))
    )
    (net (code "92") (name "unconnected-(T1B-TCT2-Pad10)") (class "Default")
      (node (ref "T1") (pin "10") (pinfunction "TCT2_10") (pintype "bidirectional"))
    )
    (net (code "93") (name "unconnected-(T2A-TCT1-Pad1)") (class "Default")
      (node (ref "T2") (pin "1") (pinfunction "TCT1_1") (pintype "bidirectional"))
    )
    (net (code "94") (name "unconnected-(T2A-TCT2-Pad4)") (class "Default")
      (node (ref "T2") (pin "4") (pinfunction "TCT2_4") (pintype "bidirectional"))
    )
    (net (code "95") (name "unconnected-(T2B-TCT1-Pad7)") (class "Default")
      (node (ref "T2") (pin "7") (pinfunction "TCT1_7") (pintype "bidirectional"))
    )
    (net (code "96") (name "unconnected-(T2B-TCT2-Pad10)") (class "Default")
      (node (ref "T2") (pin "10") (pinfunction "TCT2_10") (pintype "bidirectional"))
    )
    (net (code "97") (name "unconnected-(X1G-S-Pad7)") (class "Default")
      (node (ref "X1") (pin "7") (pinfunction "S_7") (pintype "passive"))
    )
  )
)
